# Buzzer_and_Solenoid.net
KiCad netlist of a schematic drawn in Altium Designer
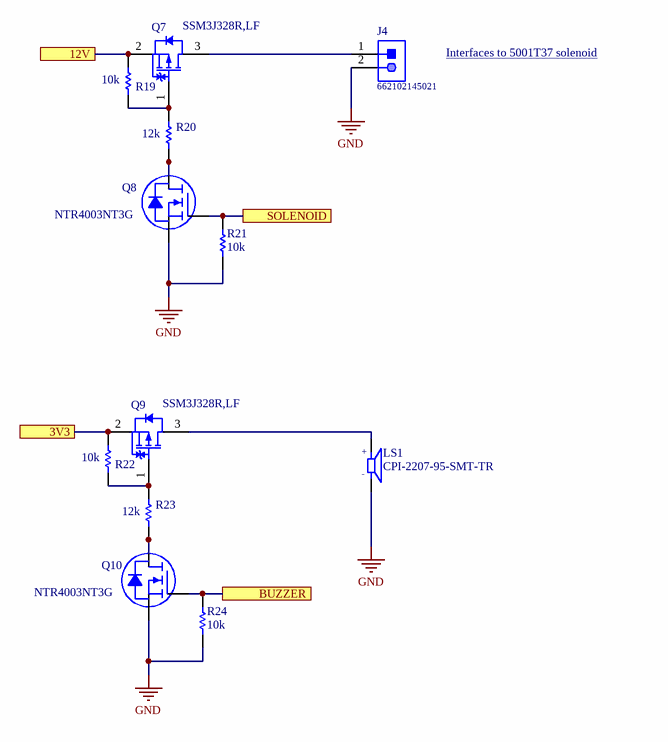
[diagram p0: Buzzer_and_Solenoid.SchDoc]

(export (version "E")
  (design (tool "Eeschema 10.0.6"))
  (components
    (comp (ref "J4")
      (value "662102145021")
      (footprint "662102145021")
      (description "SMT Male Header WR-MPC3, with SMT Solder Tabs, Right Angled, Single Row, pitch 3 mm, 2 pins")
      (fields (field (name "MANUFACTURER") "Wurth Elektronik") (field (name "PUBLISHER") "WurthElektronik"))
      (libsource (lib "Altium Content Vault") (part "WE-CN-1P-M-R2"))
    )
    (comp (ref "LS1")
      (value "CPI-2207-95-SMT-TR")
      (footprint "XDCR_CPI-2207-95-SMT-TR")
      (description "22.1 mm, 12 Vdc, 95 dB, Surface Mount, Driving Circuit, Piezo Audio Indicator Buzzer")
      (fields
        (field (name "DIGI-KEY_PART_NUMBER") "2223-CPI-2207-95-SMT-CT-ND")
        (field (name "MF") "CUI Devices")
      )
      (libsource (lib "CPI-2207-95-SMT-TR") (part "CPI-2207-95-SMT-TR"))
    )
    (comp (ref "Q7")
      (value "SSM3J328R,LF")
      (footprint "TOSH-SOT-23F_V")
      (fields (field (name "MANUFACTURER") "Toshiba"))
      (libsource (lib "Altium Content Vault") (part "PEMOS-GSD-3_C"))
    )
    (comp (ref "Q8")
      (value "NTR4003NT3G")
      (footprint "ON SEMI SOT-23-3")
      (description "MOSFET N-CH 30V 500MA SOT-23")
      (fields (field (name "MANUFACTURER") "ON Semiconductor"))
      (libsource (lib "Celestial Altium Library - altium_library") (part "ON SEMI MOSFET N-CH SOT-23-3"))
    )
    (comp (ref "Q9")
      (value "SSM3J328R,LF")
      (footprint "TOSH-SOT-23F_V")
      (fields (field (name "MANUFACTURER") "Toshiba"))
      (libsource (lib "Altium Content Vault") (part "PEMOS-GSD-3_C"))
    )
    (comp (ref "Q10")
      (value "NTR4003NT3G")
      (footprint "ON SEMI SOT-23-3")
      (description "MOSFET N-CH 30V 500MA SOT-23")
      (fields (field (name "MANUFACTURER") "ON Semiconductor"))
      (libsource (lib "Celestial Altium Library - altium_library") (part "ON SEMI MOSFET N-CH SOT-23-3"))
    )
    (comp (ref "R19")
      (value "10k")
      (footprint "RESC1609X50X30NL8T20")
      (description "Chip Resistor, 10 KOhm, +/- 1%, 100 mW, -55 to 155 degC, 0603 (1608 Metric), RoHS, Tape and Reel")
      (fields
        (field (name "MANUFACTURER") "Vishay Semiconductor")
        (field (name "Comment") "CRCW060310K0FKEA")
      )
      (libsource (lib "Altium Content Vault") (part "RES-2"))
    )
    (comp (ref "R20")
      (value "12k")
      (footprint "RESC1609X50X30LL10T20")
      (fields (field (name "MANUFACTURER") "Vishay Dale") (field (name "PART NUMBER") "CRCW060312K0FKEA"))
      (libsource (lib "Altium Content Vault") (part "RES"))
    )
    (comp (ref "R21")
      (value "10k")
      (footprint "RESC1609X50X30NL8T20")
      (description "Chip Resistor, 10 KOhm, +/- 1%, 100 mW, -55 to 155 degC, 0603 (1608 Metric), RoHS, Tape and Reel")
      (fields
        (field (name "MANUFACTURER") "Vishay Semiconductor")
        (field (name "Comment") "CRCW060310K0FKEA")
      )
      (libsource (lib "Altium Content Vault") (part "RES-2"))
    )
    (comp (ref "R22")
      (value "10k")
      (footprint "RESC1609X50X30NL8T20")
      (description "Chip Resistor, 10 KOhm, +/- 1%, 100 mW, -55 to 155 degC, 0603 (1608 Metric), RoHS, Tape and Reel")
      (fields
        (field (name "MANUFACTURER") "Vishay Semiconductor")
        (field (name "Comment") "CRCW060310K0FKEA")
      )
      (libsource (lib "Altium Content Vault") (part "RES-2"))
    )
    (comp (ref "R23")
      (value "12k")
      (footprint "RESC1609X50X30LL10T20")
      (fields (field (name "MANUFACTURER") "Vishay Dale") (field (name "PART NUMBER") "CRCW060312K0FKEA"))
      (libsource (lib "Altium Content Vault") (part "RES"))
    )
    (comp (ref "R24")
      (value "10k")
      (footprint "RESC1609X50X30NL8T20")
      (description "Chip Resistor, 10 KOhm, +/- 1%, 100 mW, -55 to 155 degC, 0603 (1608 Metric), RoHS, Tape and Reel")
      (fields
        (field (name "MANUFACTURER") "Vishay Semiconductor")
        (field (name "Comment") "CRCW060310K0FKEA")
      )
      (libsource (lib "Altium Content Vault") (part "RES-2"))
    )
  )
  (nets
    (net (code "1") (name "/3V3") (class "Default")
      (node (ref "Q9") (pin "2") (pinfunction "S_2") (pintype "passive"))
      (node (ref "R22") (pin "2") (pinfunction "2_2") (pintype "passive"))
    )
    (net (code "2") (name "/12V") (class "Default")
      (node (ref "Q7") (pin "2") (pinfunction "S_2") (pintype "passive"))
      (node (ref "R19") (pin "2") (pinfunction "2_2") (pintype "passive"))
    )
    (net (code "3") (name "/BUZZER") (class "Default")
      (node (ref "Q10") (pin "1") (pinfunction "G_1") (pintype "passive"))
      (node (ref "R24") (pin "1") (pinfunction "1_1") (pintype "passive"))
    )
    (net (code "4") (name "/SOLENOID") (class "Default")
      (node (ref "Q8") (pin "1") (pinfunction "G_1") (pintype "passive"))
      (node (ref "R21") (pin "1") (pinfunction "1_1") (pintype "passive"))
    )
    (net (code "5") (name "GND") (class "Default")
      (node (ref "J4") (pin "2") (pinfunction "2_2") (pintype "passive"))
      (node (ref "LS1") (pin "N") (pinfunction "N_N") (pintype "passive"))
      (node (ref "Q10") (pin "2") (pinfunction "S_2") (pintype "passive"))
      (node (ref "Q8") (pin "2") (pinfunction "S_2") (pintype "passive"))
      (node (ref "R21") (pin "2") (pinfunction "2_2") (pintype "passive"))
      (node (ref "R24") (pin "2") (pinfunction "2_2") (pintype "passive"))
    )
    (net (code "6") (name "Net-(Q7-D)") (class "Default")
      (node (ref "J4") (pin "1") (pinfunction "1_1") (pintype "passive"))
      (node (ref "Q7") (pin "3") (pinfunction "D_3") (pintype "passive"))
    )
    (net (code "7") (name "Net-(Q7-G)") (class "Default")
      (node (ref "Q7") (pin "1") (pinfunction "G_1") (pintype "passive"))
      (node (ref "R19") (pin "1") (pinfunction "1_1") (pintype "passive"))
      (node (ref "R20") (pin "2") (pinfunction "2_2") (pintype "passive"))
    )
    (net (code "8") (name "Net-(Q8-D)") (class "Default")
      (node (ref "Q8") (pin "3") (pinfunction "D_3") (pintype "passive"))
      (node (ref "R20") (pin "1") (pinfunction "1_1") (pintype "passive"))
    )
    (net (code "9") (name "Net-(Q9-D)") (class "Default")
      (node (ref "LS1") (pin "P") (pinfunction "P_P") (pintype "passive"))
      (node (ref "Q9") (pin "3") (pinfunction "D_3") (pintype "passive"))
    )
    (net (code "10") (name "Net-(Q9-G)") (class "Default")
      (node (ref "Q9") (pin "1") (pinfunction "G_1") (pintype "passive"))
      (node (ref "R22") (pin "1") (pinfunction "1_1") (pintype "passive"))
      (node (ref "R23") (pin "2") (pinfunction "2_2") (pintype "passive"))
    )
    (net (code "11") (name "Net-(Q10-D)") (class "Default")
      (node (ref "Q10") (pin "3") (pinfunction "D_3") (pintype "passive"))
      (node (ref "R23") (pin "1") (pinfunction "1_1") (pintype "passive"))
    )
  )
)
